# OpenBlink.net
KiCad netlist of a schematic drawn in EAGLE
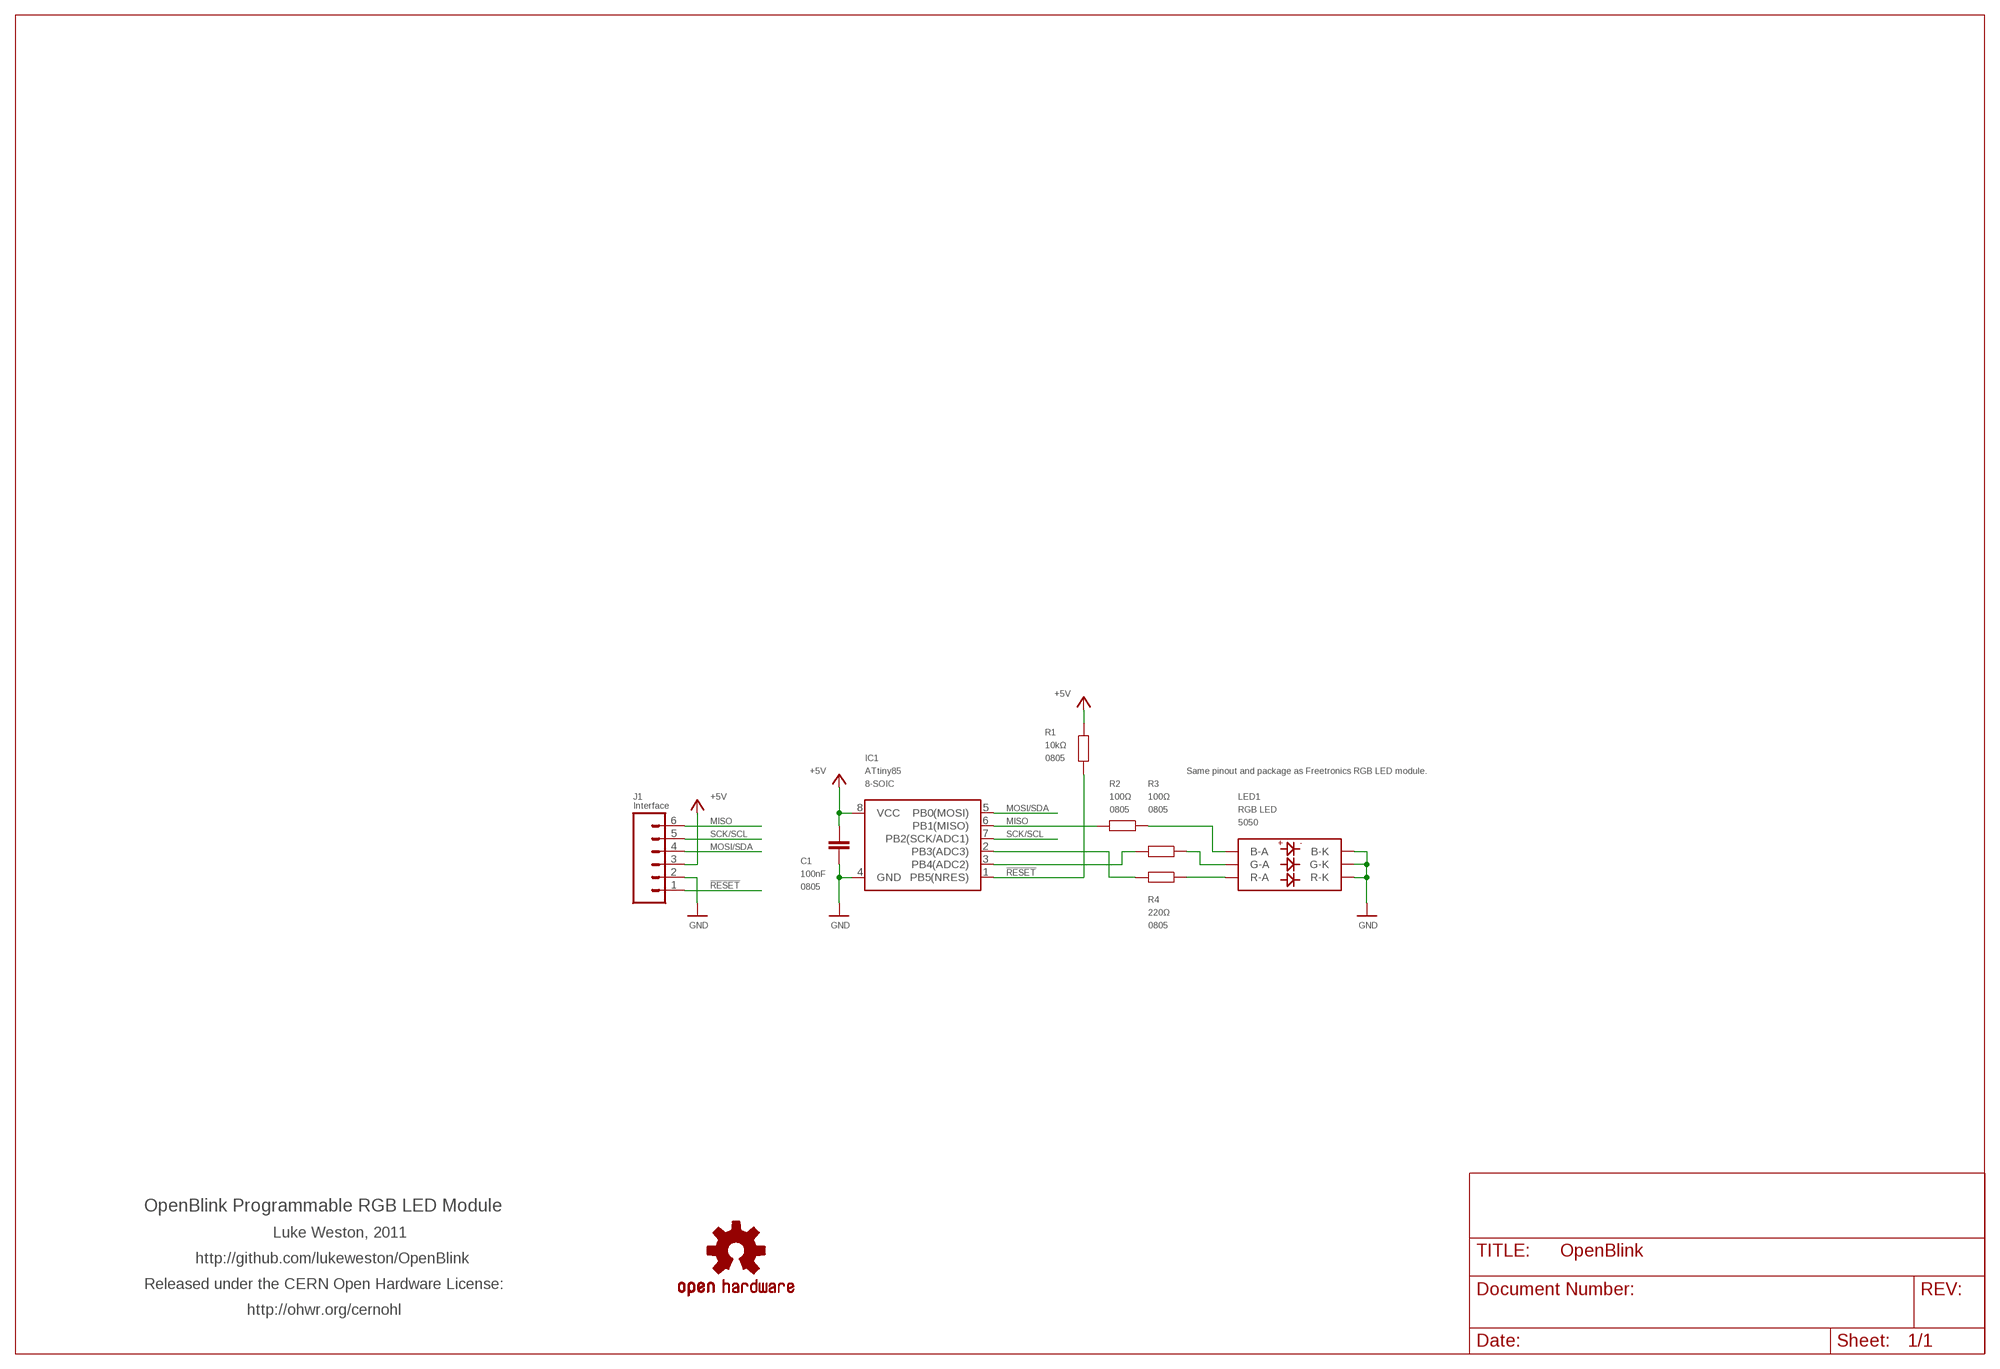
[diagram p0: schematic, sheet 1]

(export (version "E")
  (design (tool "Eeschema 10.0.6"))
  (components
    (comp (ref "C1")
      (value "100nF")
      (footprint "eagle-import:0805")
      (fields (field (name "PACKAGE") "0805"))
      (libsource (lib "eagle-import") (part "CAP0805"))
    )
    (comp (ref "IC1")
      (value "ATtiny85")
      (footprint "eagle-import:SO08-EIAJ")
      (fields (field (name "PACKAGE") "8-SOIC"))
      (libsource (lib "eagle-import") (part "ATTINY45"))
    )
    (comp (ref "J1")
      (value "Interface")
      (footprint "eagle-import:1X06")
      (libsource (lib "eagle-import") (part "M06SIP"))
    )
    (comp (ref "LED1")
      (value "RGB LED")
      (footprint "eagle-import:LED-RGB-5050")
      (fields (field (name "PACKAGE") "5050"))
      (libsource (lib "eagle-import") (part "LED-RGB-50505050"))
    )
    (comp (ref "R1")
      (value "10kΩ")
      (footprint "eagle-import:0805")
      (fields (field (name "PACKAGE") "0805"))
      (libsource (lib "eagle-import") (part "RESISTOR0805"))
    )
    (comp (ref "R2")
      (value "100Ω")
      (footprint "eagle-import:0805")
      (fields (field (name "PACKAGE") "0805"))
      (libsource (lib "eagle-import") (part "RESISTOR0805"))
    )
    (comp (ref "R3")
      (value "100Ω")
      (footprint "eagle-import:0805")
      (fields (field (name "PACKAGE") "0805"))
      (libsource (lib "eagle-import") (part "RESISTOR0805"))
    )
    (comp (ref "R4")
      (value "220Ω")
      (footprint "eagle-import:0805")
      (fields (field (name "PACKAGE") "0805"))
      (libsource (lib "eagle-import") (part "RESISTOR0805"))
    )
    (comp (ref "SY")
      (value "OSHW-LOGOS")
      (footprint "eagle-import:OSHW-LOGO-S")
      (libsource (lib "eagle-import") (part "OSHW-LOGOS"))
    )
  )
  (nets
    (net (code "1") (name "+5V") (class "Default")
      (node (ref "C1") (pin "1") (pinfunction "1_1") (pintype "passive"))
      (node (ref "IC1") (pin "8") (pinfunction "VCC_8") (pintype "bidirectional"))
      (node (ref "J1") (pin "3") (pinfunction "3_3") (pintype "passive"))
      (node (ref "R1") (pin "2") (pinfunction "2_2") (pintype "passive"))
    )
    (net (code "2") (name "/MISO") (class "Default")
      (node (ref "IC1") (pin "6") (pinfunction "PB1(MISO)_6") (pintype "bidirectional"))
      (node (ref "J1") (pin "6") (pinfunction "6_6") (pintype "passive"))
      (node (ref "R2") (pin "2") (pinfunction "2_2") (pintype "passive"))
    )
    (net (code "3") (name "/MOSI{slash}SDA") (class "Default")
      (node (ref "IC1") (pin "5") (pinfunction "PB0(MOSI)_5") (pintype "bidirectional"))
      (node (ref "J1") (pin "4") (pinfunction "4_4") (pintype "passive"))
    )
    (net (code "4") (name "/SCK{slash}SCL") (class "Default")
      (node (ref "IC1") (pin "7") (pinfunction "PB2(SCK/ADC1)_7") (pintype "bidirectional"))
      (node (ref "J1") (pin "5") (pinfunction "5_5") (pintype "passive"))
    )
    (net (code "5") (name "/~{RESET}") (class "Default")
      (node (ref "IC1") (pin "1") (pinfunction "PB5(NRES)_1") (pintype "bidirectional"))
      (node (ref "J1") (pin "1") (pinfunction "1_1") (pintype "passive"))
      (node (ref "R1") (pin "1") (pinfunction "1_1") (pintype "passive"))
    )
    (net (code "6") (name "GND") (class "Default")
      (node (ref "C1") (pin "2") (pinfunction "2_2") (pintype "passive"))
      (node (ref "IC1") (pin "4") (pinfunction "GND_4") (pintype "bidirectional"))
      (node (ref "J1") (pin "2") (pinfunction "2_2") (pintype "passive"))
      (node (ref "LED1") (pin "BK") (pinfunction "B-K_BK") (pintype "bidirectional"))
      (node (ref "LED1") (pin "GK") (pinfunction "G-K_GK") (pintype "bidirectional"))
      (node (ref "LED1") (pin "RK") (pinfunction "R-K_RK") (pintype "bidirectional"))
    )
    (net (code "7") (name "Net-(IC1-PB3(ADC3))") (class "Default")
      (node (ref "IC1") (pin "2") (pinfunction "PB3(ADC3)_2") (pintype "bidirectional"))
      (node (ref "R4") (pin "2") (pinfunction "2_2") (pintype "passive"))
    )
    (net (code "8") (name "Net-(IC1-PB4(ADC2))") (class "Default")
      (node (ref "IC1") (pin "3") (pinfunction "PB4(ADC2)_3") (pintype "bidirectional"))
      (node (ref "R3") (pin "2") (pinfunction "2_2") (pintype "passive"))
    )
    (net (code "9") (name "Net-(LED1-B-A)") (class "Default")
      (node (ref "LED1") (pin "BA") (pinfunction "B-A_BA") (pintype "bidirectional"))
      (node (ref "R2") (pin "1") (pinfunction "1_1") (pintype "passive"))
    )
    (net (code "10") (name "Net-(LED1-G-A)") (class "Default")
      (node (ref "LED1") (pin "GA") (pinfunction "G-A_GA") (pintype "bidirectional"))
      (node (ref "R3") (pin "1") (pinfunction "1_1") (pintype "passive"))
    )
    (net (code "11") (name "Net-(LED1-R-A)") (class "Default")
      (node (ref "LED1") (pin "RA") (pinfunction "R-A_RA") (pintype "bidirectional"))
      (node (ref "R4") (pin "1") (pinfunction "1_1") (pintype "passive"))
    )
  )
)
